# Rev_1.net
KiCad netlist of a schematic drawn in EAGLE
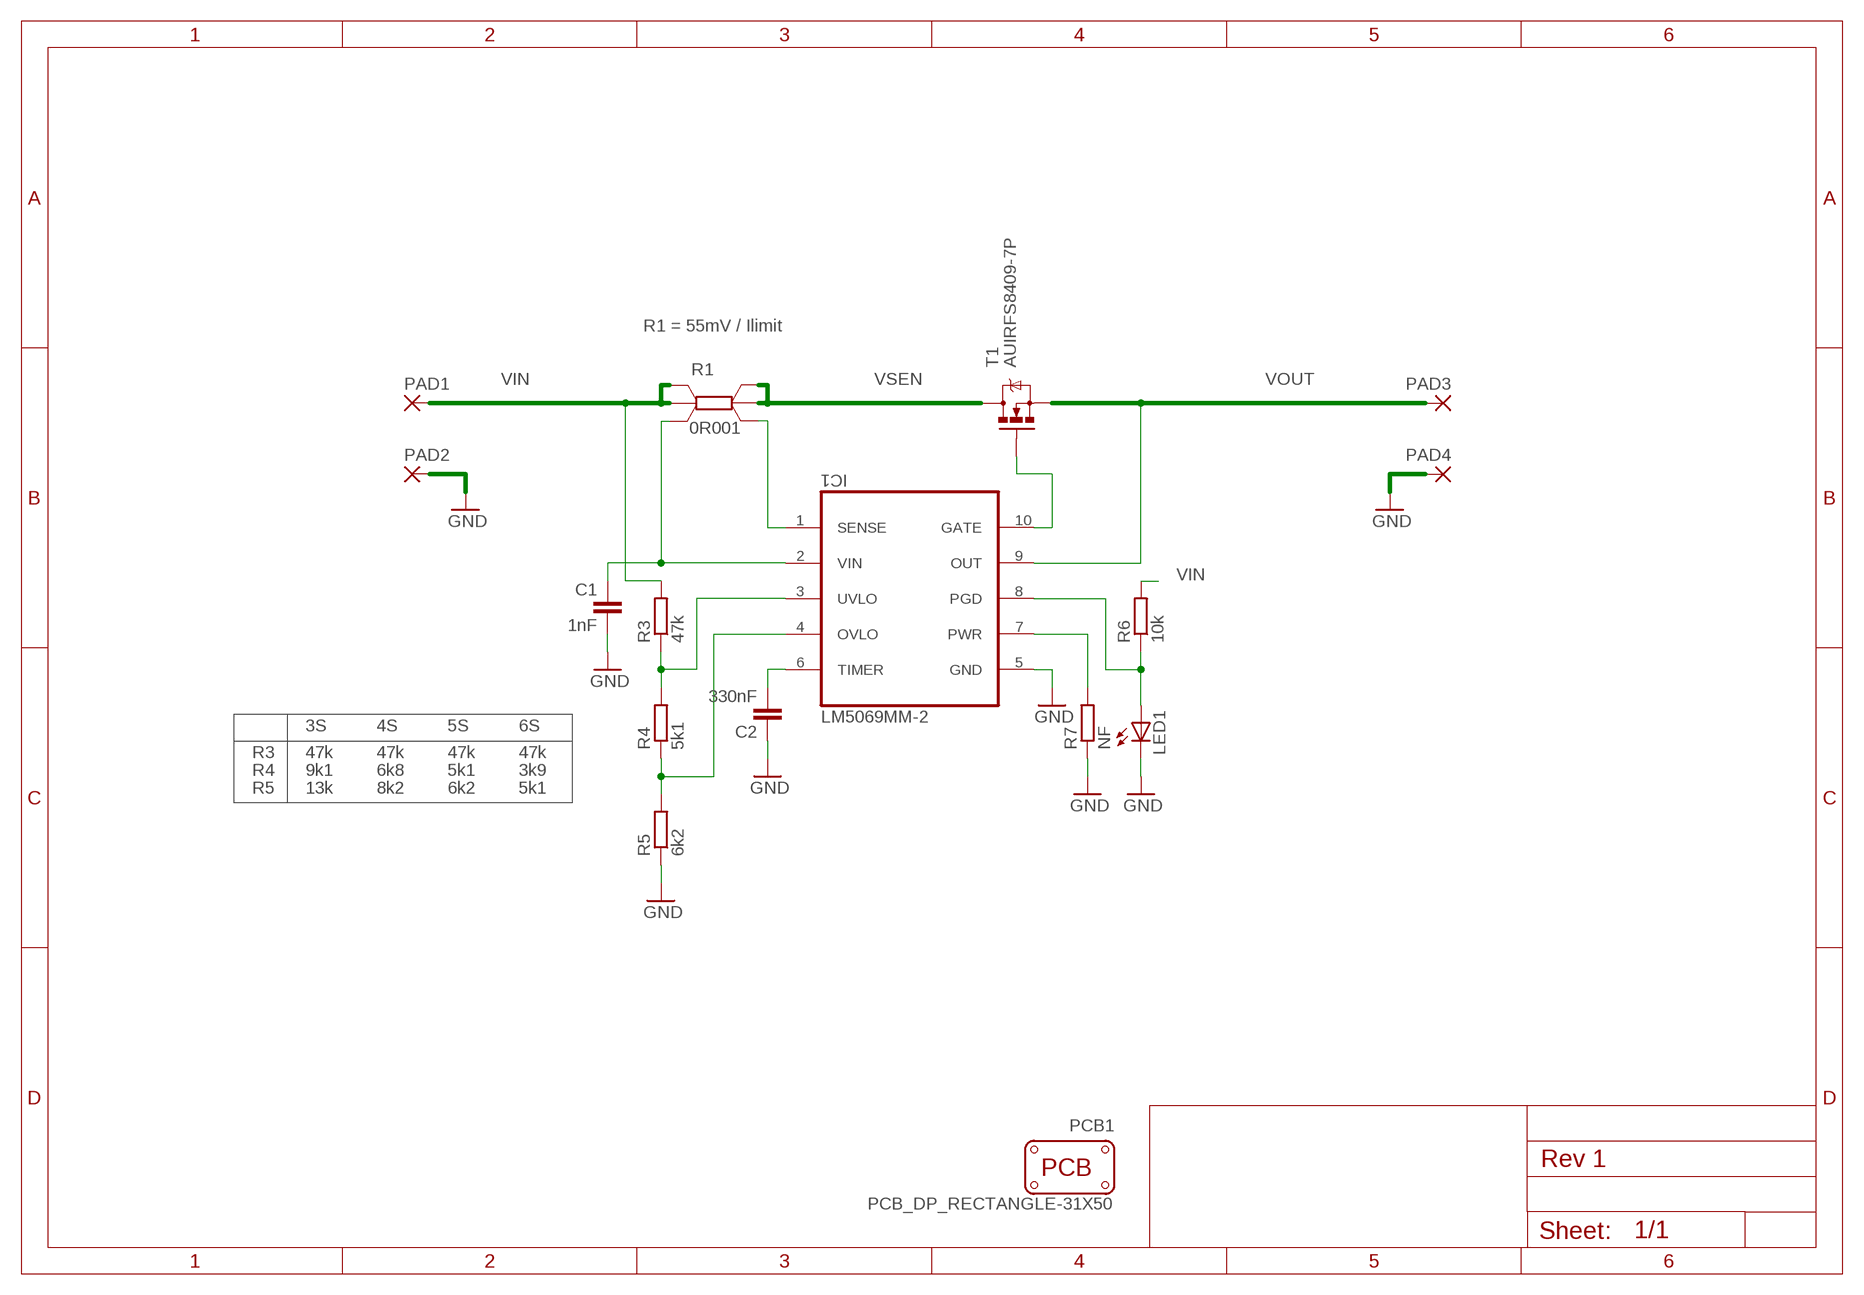
[diagram p0: schematic, sheet 1]

(export (version "E")
  (design (tool "Eeschema 10.0.6"))
  (components
    (comp (ref "C1")
      (value "1nF")
      (footprint "eagle-import:C0603")
      (fields (field (name "MF") "VISHAY") (field (name "MPN") "VJ0603Y102KXBAC31"))
      (libsource (lib "eagle-import") (part "C-EUC0603"))
    )
    (comp (ref "C2")
      (value "330nF")
      (footprint "eagle-import:C0603")
      (fields (field (name "MF") "TDK") (field (name "MPN") "C1608X7R1E334K080AC"))
      (libsource (lib "eagle-import") (part "C-EUC0603"))
    )
    (comp (ref "IC1")
      (value "LM5069MM-2")
      (footprint "eagle-import:SOP50P490X110-10N")
      (fields (field (name "MF") "TEXAS INSTRUMENTS"))
      (libsource (lib "eagle-import") (part "LM5069MM-2"))
    )
    (comp (ref "LED1")
      (value "LED-0805")
      (footprint "eagle-import:LED-805")
      (fields (field (name "MF") "ROHM") (field (name "MPN") "SML-211UTT86K"))
      (libsource (lib "eagle-import") (part "LED-0805"))
    )
    (comp (ref "PAD1")
      (value "SMD7")
      (footprint "eagle-import:SMD3,81-7,62")
      (libsource (lib "eagle-import") (part "SMD7"))
    )
    (comp (ref "PAD2")
      (value "SMD7")
      (footprint "eagle-import:SMD3,81-7,62")
      (libsource (lib "eagle-import") (part "SMD7"))
    )
    (comp (ref "PAD3")
      (value "SMD7")
      (footprint "eagle-import:SMD3,81-7,62")
      (libsource (lib "eagle-import") (part "SMD7"))
    )
    (comp (ref "PAD4")
      (value "SMD7")
      (footprint "eagle-import:SMD3,81-7,62")
      (libsource (lib "eagle-import") (part "SMD7"))
    )
    (comp (ref "PCB1")
      (value "PCB_DP_RECTANGLE-31X50")
      (footprint "eagle-import:DP5031_V1")
      (libsource (lib "eagle-import") (part "PCB_DP_RECTANGLE-31X50"))
    )
    (comp (ref "R1")
      (value "0R001")
      (footprint "eagle-import:OARS_SP_4PAD")
      (fields (field (name "MF") "INTERNATIONAL RESISTIVE") (field (name "MPN") "OARSXPR001FLF"))
      (libsource (lib "eagle-import") (part "OARS_XP"))
    )
    (comp (ref "R3")
      (value "47k")
      (footprint "eagle-import:R0603")
      (fields (field (name "MF") "YAGEO (PHYCOMP)") (field (name "MPN") "RC0603FR-0747KL"))
      (libsource (lib "eagle-import") (part "R-EU_R0603"))
    )
    (comp (ref "R4")
      (value "5k1")
      (footprint "eagle-import:R0603")
      (fields (field (name "MF") "VISHAY DRALORIC") (field (name "MPN") "CRCW02015K10FNED"))
      (libsource (lib "eagle-import") (part "R-EU_R0603"))
    )
    (comp (ref "R5")
      (value "6k2")
      (footprint "eagle-import:R0603")
      (fields (field (name "MF") "VISHAY DRALORIC") (field (name "MPN") "CRCW06036K20FKEA"))
      (libsource (lib "eagle-import") (part "R-EU_R0603"))
    )
    (comp (ref "R6")
      (value "10k")
      (footprint "eagle-import:R0603")
      (fields (field (name "MF") "TE CONNECTIVITY") (field (name "MPN") "CRGH0603J10K"))
      (libsource (lib "eagle-import") (part "R-EU_R0603"))
    )
    (comp (ref "R7")
      (value "NF")
      (footprint "eagle-import:R0603")
      (libsource (lib "eagle-import") (part "R-EU_R0603"))
    )
    (comp (ref "T1")
      (value "AUIRFS8409-7P")
      (footprint "eagle-import:TO263-6")
      (fields (field (name "MF") "INTERNATIONAL RECTIFIER"))
      (libsource (lib "eagle-import") (part "IRFS7437-7PPBF"))
    )
  )
  (nets
    (net (code "1") (name "/VIN") (class "Default")
      (node (ref "PAD1") (pin "1") (pinfunction "P_1") (pintype "passive"))
      (node (ref "R1") (pin "B1") (pinfunction "B1_B1") (pintype "passive"))
      (node (ref "R1") (pin "B2") (pinfunction "B2_B2") (pintype "passive"))
      (node (ref "R3") (pin "2") (pinfunction "2_2") (pintype "passive"))
      (node (ref "R6") (pin "2") (pinfunction "2_2") (pintype "passive"))
    )
    (net (code "2") (name "/VOUT") (class "Default")
      (node (ref "IC1") (pin "9") (pinfunction "OUT_9") (pintype "output"))
      (node (ref "PAD3") (pin "1") (pinfunction "P_1") (pintype "passive"))
      (node (ref "T1") (pin "2") (pinfunction "S_2") (pintype "passive"))
      (node (ref "T1") (pin "3") (pinfunction "S_3") (pintype "passive"))
      (node (ref "T1") (pin "4") (pinfunction "S_4") (pintype "passive"))
      (node (ref "T1") (pin "5") (pinfunction "S_5") (pintype "passive"))
      (node (ref "T1") (pin "6") (pinfunction "S_6") (pintype "passive"))
    )
    (net (code "3") (name "/VSEN") (class "Default")
      (node (ref "R1") (pin "A1") (pinfunction "A1_A1") (pintype "passive"))
      (node (ref "R1") (pin "A2") (pinfunction "A2_A2") (pintype "passive"))
      (node (ref "T1") (pin "TH") (pinfunction "D_TH") (pintype "passive"))
    )
    (net (code "4") (name "GND") (class "Default")
      (node (ref "C1") (pin "2") (pinfunction "2_2") (pintype "passive"))
      (node (ref "C2") (pin "1") (pinfunction "1_1") (pintype "passive"))
      (node (ref "IC1") (pin "5") (pinfunction "GND_5") (pintype "passive"))
      (node (ref "LED1") (pin "C") (pinfunction "C_C") (pintype "passive"))
      (node (ref "PAD2") (pin "1") (pinfunction "P_1") (pintype "passive"))
      (node (ref "PAD4") (pin "1") (pinfunction "P_1") (pintype "passive"))
      (node (ref "R5") (pin "1") (pinfunction "1_1") (pintype "passive"))
      (node (ref "R7") (pin "1") (pinfunction "1_1") (pintype "passive"))
    )
    (net (code "5") (name "Net-(IC1-GATE)") (class "Default")
      (node (ref "IC1") (pin "10") (pinfunction "GATE_10") (pintype "output"))
      (node (ref "T1") (pin "1") (pinfunction "G_1") (pintype "passive"))
    )
    (net (code "6") (name "Net-(IC1-OVLO)") (class "Default")
      (node (ref "IC1") (pin "4") (pinfunction "OVLO_4") (pintype "passive"))
      (node (ref "R4") (pin "1") (pinfunction "1_1") (pintype "passive"))
      (node (ref "R5") (pin "2") (pinfunction "2_2") (pintype "passive"))
    )
    (net (code "7") (name "Net-(IC1-PGD)") (class "Default")
      (node (ref "IC1") (pin "8") (pinfunction "PGD_8") (pintype "passive"))
      (node (ref "LED1") (pin "A") (pinfunction "A_A") (pintype "passive"))
      (node (ref "R6") (pin "1") (pinfunction "1_1") (pintype "passive"))
    )
    (net (code "8") (name "Net-(IC1-PWR)") (class "Default")
      (node (ref "IC1") (pin "7") (pinfunction "PWR_7") (pintype "power_in"))
      (node (ref "R7") (pin "2") (pinfunction "2_2") (pintype "passive"))
    )
    (net (code "9") (name "Net-(IC1-SENSE)") (class "Default")
      (node (ref "IC1") (pin "1") (pinfunction "SENSE_1") (pintype "input"))
      (node (ref "R1") (pin "AK") (pinfunction "AK_AK") (pintype "passive"))
    )
    (net (code "10") (name "Net-(IC1-TIMER)") (class "Default")
      (node (ref "C2") (pin "2") (pinfunction "2_2") (pintype "passive"))
      (node (ref "IC1") (pin "6") (pinfunction "TIMER_6") (pintype "passive"))
    )
    (net (code "11") (name "Net-(IC1-UVLO)") (class "Default")
      (node (ref "IC1") (pin "3") (pinfunction "UVLO_3") (pintype "passive"))
      (node (ref "R3") (pin "1") (pinfunction "1_1") (pintype "passive"))
      (node (ref "R4") (pin "2") (pinfunction "2_2") (pintype "passive"))
    )
    (net (code "12") (name "Net-(IC1-VIN)") (class "Default")
      (node (ref "C1") (pin "1") (pinfunction "1_1") (pintype "passive"))
      (node (ref "IC1") (pin "2") (pinfunction "VIN_2") (pintype "power_in"))
      (node (ref "R1") (pin "BK") (pinfunction "BK_BK") (pintype "passive"))
    )
  )
)
